# CAN.net
KiCad netlist of a schematic drawn in Altium Designer
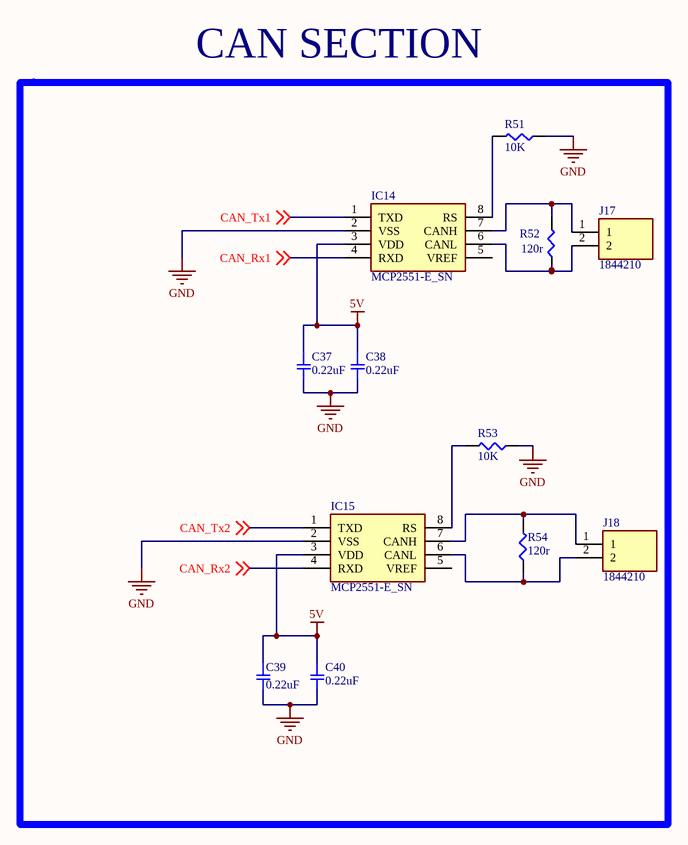
[diagram p0: CAN.SchDoc]

(export (version "E")
  (design (tool "Eeschema 10.0.6"))
  (components
    (comp (ref "C37")
      (value "0.22uF")
      (footprint "SMD-0805C")
      (description "CAP CER 0.1UF 50V X7R 0805")
      (fields
        (field (name "DIGI-KEY PART NUMBER") "490-11955-1-ND")
        (field (name "PART NUMBER") "GCD21BR71H104KA01L")
      )
      (libsource (lib "capacitor_murata_0805") (part "GCD21BR71H104KA01L"))
    )
    (comp (ref "C38")
      (value "0.22uF")
      (footprint "SMD-0805C")
      (description "CAP CER 0.1UF 50V X7R 0805")
      (fields
        (field (name "DIGI-KEY PART NUMBER") "490-11955-1-ND")
        (field (name "PART NUMBER") "GCD21BR71H104KA01L")
      )
      (libsource (lib "capacitor_murata_0805") (part "GCD21BR71H104KA01L"))
    )
    (comp (ref "C39")
      (value "0.22uF")
      (footprint "SMD-0805C")
      (description "CAP CER 0.1UF 50V X7R 0805")
      (fields
        (field (name "DIGI-KEY PART NUMBER") "490-11955-1-ND")
        (field (name "PART NUMBER") "GCD21BR71H104KA01L")
      )
      (libsource (lib "capacitor_murata_0805") (part "GCD21BR71H104KA01L"))
    )
    (comp (ref "C40")
      (value "0.22uF")
      (footprint "SMD-0805C")
      (description "CAP CER 0.1UF 50V X7R 0805")
      (fields
        (field (name "DIGI-KEY PART NUMBER") "490-11955-1-ND")
        (field (name "PART NUMBER") "GCD21BR71H104KA01L")
      )
      (libsource (lib "capacitor_murata_0805") (part "GCD21BR71H104KA01L"))
    )
    (comp (ref "IC14")
      (value "MCP2551-E_SN")
      (footprint "SamacSys:SOIC127P600X175-8N")
      (description "Integrated Circuit")
      (fields
        (field (name "MANUFACTURER_PART_NUMBER") "MCP2551-E/SN")
        (field (name "MOUSER PART NUMBER") "579-MCP2551-E/SN")
      )
      (libsource (lib "*") (part "MCP2551-E_SN"))
    )
    (comp (ref "IC15")
      (value "MCP2551-E_SN")
      (footprint "SamacSys:SOIC127P600X175-8N")
      (description "Integrated Circuit")
      (fields
        (field (name "MANUFACTURER_PART_NUMBER") "MCP2551-E/SN")
        (field (name "MOUSER PART NUMBER") "579-MCP2551-E/SN")
      )
      (libsource (lib "*") (part "MCP2551-E_SN"))
    )
    (comp (ref "J17")
      (value "1844210")
      (footprint "SamacSys:SHDRRA2W80P0X350_1X2_840X920X825P")
      (description "Connector")
      (fields (field (name "MOUSER PART NUMBER") "651-1844210"))
      (libsource (lib "*") (part "1844210"))
    )
    (comp (ref "J18")
      (value "1844210")
      (footprint "SamacSys:SHDRRA2W80P0X350_1X2_840X920X825P")
      (description "Connector")
      (fields (field (name "MOUSER PART NUMBER") "651-1844210"))
      (libsource (lib "*") (part "1844210"))
    )
    (comp (ref "R51")
      (value "10K")
      (footprint "SMD-0805-RES")
      (description "RES SMD 1K OHM 1% 1/8W 0805")
      (fields
        (field (name "PART NUMBER") "ERJ-6ENF1001V")
        (field (name "DIGI-KEY PART NUMBER") "P1.00KCCT-ND")
      )
      (libsource (lib "Panasonic_ERJ_0805") (part "ERJ-6ENF1001V"))
    )
    (comp (ref "R52")
      (value "120r")
      (footprint "SMD-0805-RES")
      (description "RES SMD 1K OHM 1% 1/8W 0805")
      (fields
        (field (name "PART NUMBER") "ERJ-6ENF1001V")
        (field (name "DIGI-KEY PART NUMBER") "P1.00KCCT-ND")
      )
      (libsource (lib "Panasonic_ERJ_0805") (part "ERJ-6ENF1001V"))
    )
    (comp (ref "R53")
      (value "10K")
      (footprint "SMD-0805-RES")
      (description "RES SMD 1K OHM 1% 1/8W 0805")
      (fields
        (field (name "PART NUMBER") "ERJ-6ENF1001V")
        (field (name "DIGI-KEY PART NUMBER") "P1.00KCCT-ND")
      )
      (libsource (lib "Panasonic_ERJ_0805") (part "ERJ-6ENF1001V"))
    )
    (comp (ref "R54")
      (value "120r")
      (footprint "SMD-0805-RES")
      (description "RES SMD 1K OHM 1% 1/8W 0805")
      (fields
        (field (name "PART NUMBER") "ERJ-6ENF1001V")
        (field (name "DIGI-KEY PART NUMBER") "P1.00KCCT-ND")
      )
      (libsource (lib "Panasonic_ERJ_0805") (part "ERJ-6ENF1001V"))
    )
  )
  (nets
    (net (code "1") (name "5V") (class "Default")
      (node (ref "C37") (pin "1") (pinfunction "1_1") (pintype "passive"))
      (node (ref "C38") (pin "1") (pinfunction "1_1") (pintype "passive"))
      (node (ref "C39") (pin "1") (pinfunction "1_1") (pintype "passive"))
      (node (ref "C40") (pin "1") (pinfunction "1_1") (pintype "passive"))
      (node (ref "IC14") (pin "3") (pinfunction "VDD_3") (pintype "passive"))
      (node (ref "IC15") (pin "3") (pinfunction "VDD_3") (pintype "passive"))
    )
    (net (code "2") (name "CAN_Rx1") (class "Default")
      (node (ref "IC14") (pin "4") (pinfunction "RXD_4") (pintype "passive"))
    )
    (net (code "3") (name "CAN_Rx2") (class "Default")
      (node (ref "IC15") (pin "4") (pinfunction "RXD_4") (pintype "passive"))
    )
    (net (code "4") (name "CAN_Tx1") (class "Default")
      (node (ref "IC14") (pin "1") (pinfunction "TXD_1") (pintype "passive"))
    )
    (net (code "5") (name "CAN_Tx2") (class "Default")
      (node (ref "IC15") (pin "1") (pinfunction "TXD_1") (pintype "passive"))
    )
    (net (code "6") (name "GND") (class "Default")
      (node (ref "C37") (pin "2") (pinfunction "2_2") (pintype "passive"))
      (node (ref "C38") (pin "2") (pinfunction "2_2") (pintype "passive"))
      (node (ref "C39") (pin "2") (pinfunction "2_2") (pintype "passive"))
      (node (ref "C40") (pin "2") (pinfunction "2_2") (pintype "passive"))
      (node (ref "IC14") (pin "2") (pinfunction "VSS_2") (pintype "passive"))
      (node (ref "IC15") (pin "2") (pinfunction "VSS_2") (pintype "passive"))
      (node (ref "R51") (pin "1") (pinfunction "1_1") (pintype "passive"))
      (node (ref "R53") (pin "1") (pinfunction "1_1") (pintype "passive"))
    )
    (net (code "7") (name "Net-(IC14-CANH)") (class "Default")
      (node (ref "IC14") (pin "7") (pinfunction "CANH_7") (pintype "passive"))
      (node (ref "J17") (pin "1") (pinfunction "1_1") (pintype "passive"))
      (node (ref "R52") (pin "2") (pinfunction "2_2") (pintype "passive"))
    )
    (net (code "8") (name "Net-(IC14-CANL)") (class "Default")
      (node (ref "IC14") (pin "6") (pinfunction "CANL_6") (pintype "passive"))
      (node (ref "J17") (pin "2") (pinfunction "2_2") (pintype "passive"))
      (node (ref "R52") (pin "1") (pinfunction "1_1") (pintype "passive"))
    )
    (net (code "9") (name "Net-(IC14-RS)") (class "Default")
      (node (ref "IC14") (pin "8") (pinfunction "RS_8") (pintype "passive"))
      (node (ref "R51") (pin "2") (pinfunction "2_2") (pintype "passive"))
    )
    (net (code "10") (name "Net-(IC15-CANH)") (class "Default")
      (node (ref "IC15") (pin "7") (pinfunction "CANH_7") (pintype "passive"))
      (node (ref "J18") (pin "1") (pinfunction "1_1") (pintype "passive"))
      (node (ref "R54") (pin "2") (pinfunction "2_2") (pintype "passive"))
    )
    (net (code "11") (name "Net-(IC15-CANL)") (class "Default")
      (node (ref "IC15") (pin "6") (pinfunction "CANL_6") (pintype "passive"))
      (node (ref "J18") (pin "2") (pinfunction "2_2") (pintype "passive"))
      (node (ref "R54") (pin "1") (pinfunction "1_1") (pintype "passive"))
    )
    (net (code "12") (name "Net-(IC15-RS)") (class "Default")
      (node (ref "IC15") (pin "8") (pinfunction "RS_8") (pintype "passive"))
      (node (ref "R53") (pin "2") (pinfunction "2_2") (pintype "passive"))
    )
    (net (code "13") (name "unconnected-(IC14-VREF-Pad5)") (class "Default")
      (node (ref "IC14") (pin "5") (pinfunction "VREF_5") (pintype "passive"))
    )
    (net (code "14") (name "unconnected-(IC15-VREF-Pad5)") (class "Default")
      (node (ref "IC15") (pin "5") (pinfunction "VREF_5") (pintype "passive"))
    )
  )
)
